# ctecka_brana.net
KiCad netlist of a schematic drawn in EAGLE
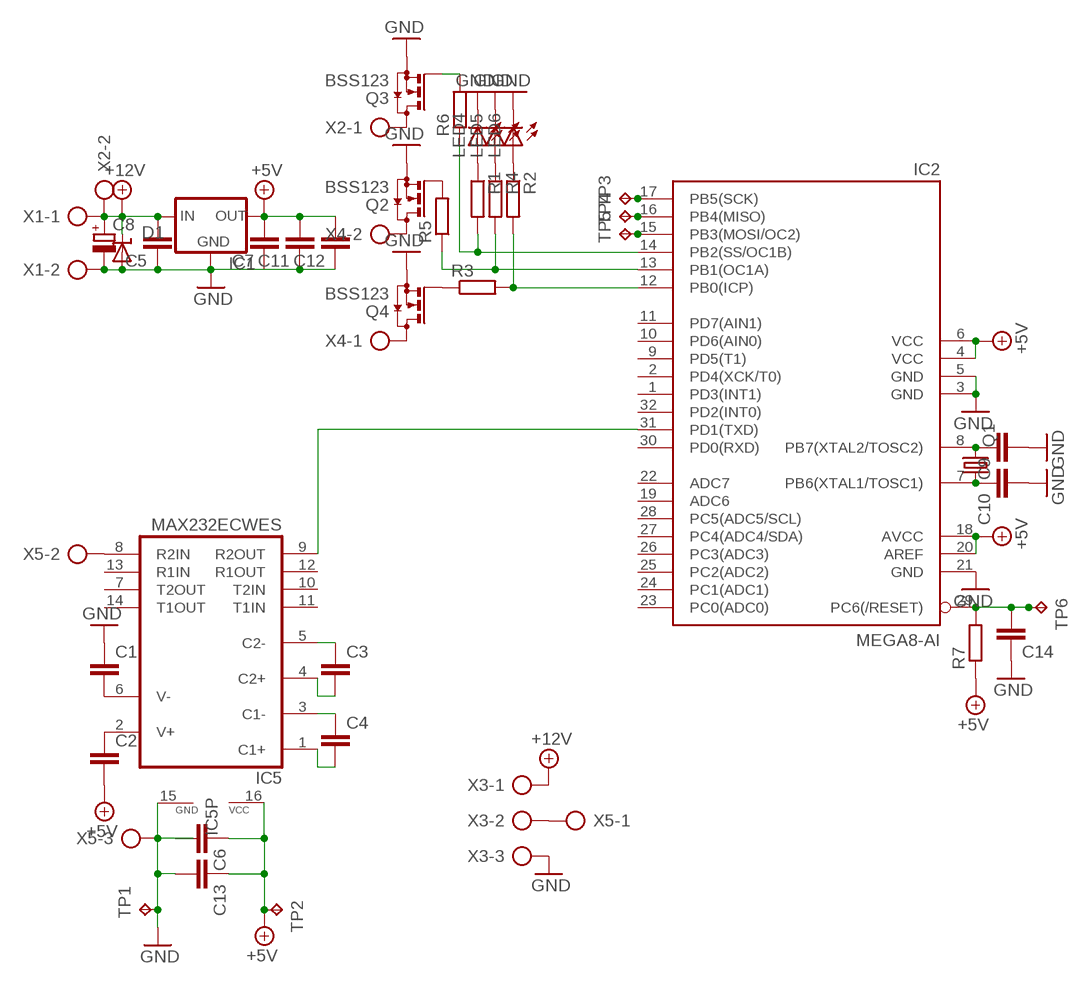
[diagram p0: schematic, sheet 1]

(export (version "E")
  (design (tool "Eeschema 10.0.6"))
  (components
    (comp (ref "C1")
      (value "C-EUC0603")
      (footprint "eagle-import:C0603")
      (libsource (lib "eagle-import") (part "C-EUC0603"))
    )
    (comp (ref "C2")
      (value "C-EUC0603")
      (footprint "eagle-import:C0603")
      (libsource (lib "eagle-import") (part "C-EUC0603"))
    )
    (comp (ref "C3")
      (value "C-EUC0603")
      (footprint "eagle-import:C0603")
      (libsource (lib "eagle-import") (part "C-EUC0603"))
    )
    (comp (ref "C4")
      (value "C-EUC0603")
      (footprint "eagle-import:C0603")
      (libsource (lib "eagle-import") (part "C-EUC0603"))
    )
    (comp (ref "C5")
      (value "C-EUC0603")
      (footprint "eagle-import:C0603")
      (libsource (lib "eagle-import") (part "C-EUC0603"))
    )
    (comp (ref "C6")
      (value "C-EUC0603")
      (footprint "eagle-import:C0603")
      (libsource (lib "eagle-import") (part "C-EUC0603"))
    )
    (comp (ref "C7")
      (value "C-EUC0603")
      (footprint "eagle-import:C0603")
      (libsource (lib "eagle-import") (part "C-EUC0603"))
    )
    (comp (ref "C8")
      (value "CPOL-EUSMCD")
      (footprint "eagle-import:SMC_D")
      (libsource (lib "eagle-import") (part "CPOL-EUSMCD"))
    )
    (comp (ref "C9")
      (value "C-EUC0603")
      (footprint "eagle-import:C0603")
      (libsource (lib "eagle-import") (part "C-EUC0603"))
    )
    (comp (ref "C10")
      (value "C-EUC0603")
      (footprint "eagle-import:C0603")
      (libsource (lib "eagle-import") (part "C-EUC0603"))
    )
    (comp (ref "C11")
      (value "C-EUC0603")
      (footprint "eagle-import:C0603")
      (libsource (lib "eagle-import") (part "C-EUC0603"))
    )
    (comp (ref "C12")
      (value "C-EUC0603")
      (footprint "eagle-import:C0603")
      (libsource (lib "eagle-import") (part "C-EUC0603"))
    )
    (comp (ref "C13")
      (value "C-EUC0603")
      (footprint "eagle-import:C0603")
      (libsource (lib "eagle-import") (part "C-EUC0603"))
    )
    (comp (ref "C14")
      (value "C-EUC0603")
      (footprint "eagle-import:C0603")
      (libsource (lib "eagle-import") (part "C-EUC0603"))
    )
    (comp (ref "D1")
      (value "SUPPRESSOR-SMBG")
      (footprint "eagle-import:SMBG")
      (libsource (lib "eagle-import") (part "SUPPRESSOR-SMBG"))
    )
    (comp (ref "IC1")
      (value "78LXXF")
      (footprint "eagle-import:SOT89R")
      (libsource (lib "eagle-import") (part "78LXXF"))
    )
    (comp (ref "IC2")
      (value "MEGA8-AI")
      (footprint "eagle-import:TQFP32-08")
      (libsource (lib "eagle-import") (part "MEGA8-AI"))
    )
    (comp (ref "IC5")
      (value "MAX232ECWES")
      (footprint "eagle-import:SO16")
      (libsource (lib "eagle-import") (part "MAX232ECWES"))
    )
    (comp (ref "LED4")
      (value "LEDCHIP-LED0805")
      (footprint "eagle-import:CHIP-LED0805")
      (libsource (lib "eagle-import") (part "LEDCHIP-LED0805"))
    )
    (comp (ref "LED5")
      (value "LEDCHIP-LED0805")
      (footprint "eagle-import:CHIP-LED0805")
      (libsource (lib "eagle-import") (part "LEDCHIP-LED0805"))
    )
    (comp (ref "LED6")
      (value "LEDCHIP-LED0805")
      (footprint "eagle-import:CHIP-LED0805")
      (libsource (lib "eagle-import") (part "LEDCHIP-LED0805"))
    )
    (comp (ref "Q1")
      (value "CRYSTALCTS406")
      (footprint "eagle-import:CTS406")
      (libsource (lib "eagle-import") (part "CRYSTALCTS406"))
    )
    (comp (ref "Q2")
      (value "BSS123")
      (footprint "eagle-import:SOT23")
      (libsource (lib "eagle-import") (part "BSS123"))
    )
    (comp (ref "Q3")
      (value "BSS123")
      (footprint "eagle-import:SOT23")
      (libsource (lib "eagle-import") (part "BSS123"))
    )
    (comp (ref "Q4")
      (value "BSS123")
      (footprint "eagle-import:SOT23")
      (libsource (lib "eagle-import") (part "BSS123"))
    )
    (comp (ref "R1")
      (value "R-EU_R0603")
      (footprint "eagle-import:R0603")
      (libsource (lib "eagle-import") (part "R-EU_R0603"))
    )
    (comp (ref "R2")
      (value "R-EU_R0603")
      (footprint "eagle-import:R0603")
      (libsource (lib "eagle-import") (part "R-EU_R0603"))
    )
    (comp (ref "R3")
      (value "R-EU_R0603")
      (footprint "eagle-import:R0603")
      (libsource (lib "eagle-import") (part "R-EU_R0603"))
    )
    (comp (ref "R4")
      (value "R-EU_R0603")
      (footprint "eagle-import:R0603")
      (libsource (lib "eagle-import") (part "R-EU_R0603"))
    )
    (comp (ref "R5")
      (value "R-EU_R0603")
      (footprint "eagle-import:R0603")
      (libsource (lib "eagle-import") (part "R-EU_R0603"))
    )
    (comp (ref "R6")
      (value "R-EU_R0603")
      (footprint "eagle-import:R0603")
      (libsource (lib "eagle-import") (part "R-EU_R0603"))
    )
    (comp (ref "R7")
      (value "R-EU_R0603")
      (footprint "eagle-import:R0603")
      (libsource (lib "eagle-import") (part "R-EU_R0603"))
    )
    (comp (ref "TP1")
      (value "TPB1,27")
      (footprint "eagle-import:B1,27")
      (libsource (lib "eagle-import") (part "TPB1,27"))
    )
    (comp (ref "TP2")
      (value "TPB1,27")
      (footprint "eagle-import:B1,27")
      (libsource (lib "eagle-import") (part "TPB1,27"))
    )
    (comp (ref "TP3")
      (value "TPB1,27")
      (footprint "eagle-import:B1,27")
      (libsource (lib "eagle-import") (part "TPB1,27"))
    )
    (comp (ref "TP4")
      (value "TPB1,27")
      (footprint "eagle-import:B1,27")
      (libsource (lib "eagle-import") (part "TPB1,27"))
    )
    (comp (ref "TP5")
      (value "TPB1,27")
      (footprint "eagle-import:B1,27")
      (libsource (lib "eagle-import") (part "TPB1,27"))
    )
    (comp (ref "TP6")
      (value "TPB1,27")
      (footprint "eagle-import:B1,27")
      (libsource (lib "eagle-import") (part "TPB1,27"))
    )
    (comp (ref "X1")
      (value "AK500/2")
      (footprint "eagle-import:AK500_2")
      (libsource (lib "eagle-import") (part "AK500/2"))
    )
    (comp (ref "X2")
      (value "AK500/2")
      (footprint "eagle-import:AK500_2")
      (libsource (lib "eagle-import") (part "AK500/2"))
    )
    (comp (ref "X3")
      (value "AK500/3")
      (footprint "eagle-import:AK500_3")
      (libsource (lib "eagle-import") (part "AK500/3"))
    )
    (comp (ref "X4")
      (value "AK500/2")
      (footprint "eagle-import:AK500_2")
      (libsource (lib "eagle-import") (part "AK500/2"))
    )
    (comp (ref "X5")
      (value "AK500/3")
      (footprint "eagle-import:AK500_3")
      (libsource (lib "eagle-import") (part "AK500/3"))
    )
  )
  (nets
    (net (code "1") (name "+5V") (class "Default")
      (node (ref "C11") (pin "2") (pinfunction "2_2") (pintype "passive"))
      (node (ref "C12") (pin "2") (pinfunction "2_2") (pintype "passive"))
      (node (ref "C13") (pin "1") (pinfunction "1_1") (pintype "passive"))
      (node (ref "C2") (pin "2") (pinfunction "2_2") (pintype "passive"))
      (node (ref "C6") (pin "1") (pinfunction "1_1") (pintype "passive"))
      (node (ref "C7") (pin "2") (pinfunction "2_2") (pintype "passive"))
      (node (ref "IC1") (pin "2") (pinfunction "OUT_2") (pintype "passive"))
      (node (ref "IC2") (pin "18") (pinfunction "AVCC_18") (pintype "power_in"))
      (node (ref "IC2") (pin "20") (pinfunction "AREF_20") (pintype "passive"))
      (node (ref "IC2") (pin "4") (pinfunction "VCC_4") (pintype "power_in"))
      (node (ref "IC2") (pin "6") (pinfunction "VCC_6") (pintype "power_in"))
      (node (ref "IC5") (pin "16") (pinfunction "VCC_16") (pintype "power_in"))
      (node (ref "R7") (pin "1") (pinfunction "1_1") (pintype "passive"))
      (node (ref "TP2") (pin "TP") (pinfunction "TP_TP") (pintype "input"))
    )
    (net (code "2") (name "+12V") (class "Default")
      (node (ref "C5") (pin "2") (pinfunction "2_2") (pintype "passive"))
      (node (ref "C8") (pin "+") (pinfunction "+_+") (pintype "passive"))
      (node (ref "D1") (pin "C") (pinfunction "C_C") (pintype "passive"))
      (node (ref "IC1") (pin "1") (pinfunction "IN_1") (pintype "input"))
      (node (ref "X1") (pin "1") (pinfunction "KL_1") (pintype "passive"))
      (node (ref "X2") (pin "2") (pinfunction "KL_2") (pintype "passive"))
      (node (ref "X3") (pin "1") (pinfunction "KL_1") (pintype "passive"))
    )
    (net (code "3") (name "GND") (class "Default")
      (node (ref "C1") (pin "1") (pinfunction "1_1") (pintype "passive"))
      (node (ref "C10") (pin "2") (pinfunction "2_2") (pintype "passive"))
      (node (ref "C11") (pin "1") (pinfunction "1_1") (pintype "passive"))
      (node (ref "C12") (pin "1") (pinfunction "1_1") (pintype "passive"))
      (node (ref "C13") (pin "2") (pinfunction "2_2") (pintype "passive"))
      (node (ref "C14") (pin "1") (pinfunction "1_1") (pintype "passive"))
      (node (ref "C5") (pin "1") (pinfunction "1_1") (pintype "passive"))
      (node (ref "C6") (pin "2") (pinfunction "2_2") (pintype "passive"))
      (node (ref "C7") (pin "1") (pinfunction "1_1") (pintype "passive"))
      (node (ref "C8") (pin "-") (pinfunction "-_-") (pintype "passive"))
      (node (ref "C9") (pin "2") (pinfunction "2_2") (pintype "passive"))
      (node (ref "D1") (pin "A") (pinfunction "A_A") (pintype "passive"))
      (node (ref "IC1") (pin "3") (pinfunction "GND_3") (pintype "input"))
      (node (ref "IC2") (pin "21") (pinfunction "GND_21") (pintype "power_in"))
      (node (ref "IC2") (pin "3") (pinfunction "GND_3") (pintype "power_in"))
      (node (ref "IC2") (pin "5") (pinfunction "GND_5") (pintype "power_in"))
      (node (ref "IC5") (pin "15") (pinfunction "GND_15") (pintype "power_in"))
      (node (ref "LED4") (pin "C") (pinfunction "C_C") (pintype "passive"))
      (node (ref "LED5") (pin "C") (pinfunction "C_C") (pintype "passive"))
      (node (ref "LED6") (pin "C") (pinfunction "C_C") (pintype "passive"))
      (node (ref "Q2") (pin "2") (pinfunction "S_2") (pintype "passive"))
      (node (ref "Q3") (pin "2") (pinfunction "S_2") (pintype "passive"))
      (node (ref "Q4") (pin "2") (pinfunction "S_2") (pintype "passive"))
      (node (ref "TP1") (pin "TP") (pinfunction "TP_TP") (pintype "input"))
      (node (ref "X1") (pin "2") (pinfunction "KL_2") (pintype "passive"))
      (node (ref "X3") (pin "3") (pinfunction "KL_3") (pintype "passive"))
      (node (ref "X5") (pin "3") (pinfunction "KL_3") (pintype "passive"))
    )
    (net (code "4") (name "Net-(IC2-PB0(ICP))") (class "Default")
      (node (ref "IC2") (pin "12") (pinfunction "PB0(ICP)_12") (pintype "bidirectional"))
      (node (ref "R2") (pin "2") (pinfunction "2_2") (pintype "passive"))
      (node (ref "R3") (pin "2") (pinfunction "2_2") (pintype "passive"))
    )
    (net (code "5") (name "Net-(IC2-PB1(OC1A))") (class "Default")
      (node (ref "IC2") (pin "13") (pinfunction "PB1(OC1A)_13") (pintype "bidirectional"))
      (node (ref "R4") (pin "2") (pinfunction "2_2") (pintype "passive"))
      (node (ref "R5") (pin "1") (pinfunction "1_1") (pintype "passive"))
    )
    (net (code "6") (name "Net-(IC2-PB2(SS{slash}OC1B))") (class "Default")
      (node (ref "IC2") (pin "14") (pinfunction "PB2(SS/OC1B)_14") (pintype "bidirectional"))
      (node (ref "R1") (pin "2") (pinfunction "2_2") (pintype "passive"))
      (node (ref "R6") (pin "1") (pinfunction "1_1") (pintype "passive"))
    )
    (net (code "7") (name "Net-(IC2-PB3(MOSI{slash}OC2))") (class "Default")
      (node (ref "IC2") (pin "15") (pinfunction "PB3(MOSI/OC2)_15") (pintype "bidirectional"))
      (node (ref "TP5") (pin "TP") (pinfunction "TP_TP") (pintype "input"))
    )
    (net (code "8") (name "Net-(IC2-PB4(MISO))") (class "Default")
      (node (ref "IC2") (pin "16") (pinfunction "PB4(MISO)_16") (pintype "bidirectional"))
      (node (ref "TP4") (pin "TP") (pinfunction "TP_TP") (pintype "input"))
    )
    (net (code "9") (name "Net-(IC2-PB5(SCK))") (class "Default")
      (node (ref "IC2") (pin "17") (pinfunction "PB5(SCK)_17") (pintype "bidirectional"))
      (node (ref "TP3") (pin "TP") (pinfunction "TP_TP") (pintype "input"))
    )
    (net (code "10") (name "Net-(IC2-PB6(XTAL1{slash}TOSC1))") (class "Default")
      (node (ref "C10") (pin "1") (pinfunction "1_1") (pintype "passive"))
      (node (ref "IC2") (pin "7") (pinfunction "PB6(XTAL1/TOSC1)_7") (pintype "bidirectional"))
      (node (ref "Q1") (pin "1") (pinfunction "1_1") (pintype "passive"))
    )
    (net (code "11") (name "Net-(IC2-PB7(XTAL2{slash}TOSC2))") (class "Default")
      (node (ref "C9") (pin "1") (pinfunction "1_1") (pintype "passive"))
      (node (ref "IC2") (pin "8") (pinfunction "PB7(XTAL2/TOSC2)_8") (pintype "bidirectional"))
      (node (ref "Q1") (pin "3") (pinfunction "2_3") (pintype "passive"))
    )
    (net (code "12") (name "Net-(IC2-PC6({slash}RESET))") (class "Default")
      (node (ref "C14") (pin "2") (pinfunction "2_2") (pintype "passive"))
      (node (ref "IC2") (pin "29") (pinfunction "PC6(/RESET)_29") (pintype "bidirectional"))
      (node (ref "R7") (pin "2") (pinfunction "2_2") (pintype "passive"))
      (node (ref "TP6") (pin "TP") (pinfunction "TP_TP") (pintype "input"))
    )
    (net (code "13") (name "Net-(IC2-PD1(TXD))") (class "Default")
      (node (ref "IC2") (pin "31") (pinfunction "PD1(TXD)_31") (pintype "bidirectional"))
      (node (ref "IC5") (pin "9") (pinfunction "R2OUT_9") (pintype "output"))
    )
    (net (code "14") (name "Net-(IC5A-C1+)") (class "Default")
      (node (ref "C4") (pin "2") (pinfunction "2_2") (pintype "passive"))
      (node (ref "IC5") (pin "1") (pinfunction "C1+_1") (pintype "bidirectional"))
    )
    (net (code "15") (name "Net-(IC5A-C1-)") (class "Default")
      (node (ref "C4") (pin "1") (pinfunction "1_1") (pintype "passive"))
      (node (ref "IC5") (pin "3") (pinfunction "C1-_3") (pintype "bidirectional"))
    )
    (net (code "16") (name "Net-(IC5A-C2+)") (class "Default")
      (node (ref "C3") (pin "2") (pinfunction "2_2") (pintype "passive"))
      (node (ref "IC5") (pin "4") (pinfunction "C2+_4") (pintype "bidirectional"))
    )
    (net (code "17") (name "Net-(IC5A-C2-)") (class "Default")
      (node (ref "C3") (pin "1") (pinfunction "1_1") (pintype "passive"))
      (node (ref "IC5") (pin "5") (pinfunction "C2-_5") (pintype "bidirectional"))
    )
    (net (code "18") (name "Net-(IC5A-R2IN)") (class "Default")
      (node (ref "IC5") (pin "8") (pinfunction "R2IN_8") (pintype "input"))
      (node (ref "X5") (pin "2") (pinfunction "KL_2") (pintype "passive"))
    )
    (net (code "19") (name "Net-(IC5A-V+)") (class "Default")
      (node (ref "C2") (pin "1") (pinfunction "1_1") (pintype "passive"))
      (node (ref "IC5") (pin "2") (pinfunction "V+_2") (pintype "bidirectional"))
    )
    (net (code "20") (name "Net-(IC5A-V-)") (class "Default")
      (node (ref "C1") (pin "2") (pinfunction "2_2") (pintype "passive"))
      (node (ref "IC5") (pin "6") (pinfunction "V-_6") (pintype "bidirectional"))
    )
    (net (code "21") (name "Net-(LED4-PadA)") (class "Default")
      (node (ref "LED4") (pin "A") (pinfunction "A_A") (pintype "passive"))
      (node (ref "R1") (pin "1") (pinfunction "1_1") (pintype "passive"))
    )
    (net (code "22") (name "Net-(LED5-PadA)") (class "Default")
      (node (ref "LED5") (pin "A") (pinfunction "A_A") (pintype "passive"))
      (node (ref "R4") (pin "1") (pinfunction "1_1") (pintype "passive"))
    )
    (net (code "23") (name "Net-(LED6-PadA)") (class "Default")
      (node (ref "LED6") (pin "A") (pinfunction "A_A") (pintype "passive"))
      (node (ref "R2") (pin "1") (pinfunction "1_1") (pintype "passive"))
    )
    (net (code "24") (name "Net-(Q2-D)") (class "Default")
      (node (ref "Q2") (pin "3") (pinfunction "D_3") (pintype "passive"))
      (node (ref "X4") (pin "2") (pinfunction "KL_2") (pintype "passive"))
    )
    (net (code "25") (name "Net-(Q2-G)") (class "Default")
      (node (ref "Q2") (pin "1") (pinfunction "G_1") (pintype "passive"))
      (node (ref "R5") (pin "2") (pinfunction "2_2") (pintype "passive"))
    )
    (net (code "26") (name "Net-(Q3-D)") (class "Default")
      (node (ref "Q3") (pin "3") (pinfunction "D_3") (pintype "passive"))
      (node (ref "X2") (pin "1") (pinfunction "KL_1") (pintype "passive"))
    )
    (net (code "27") (name "Net-(Q3-G)") (class "Default")
      (node (ref "Q3") (pin "1") (pinfunction "G_1") (pintype "passive"))
      (node (ref "R6") (pin "2") (pinfunction "2_2") (pintype "passive"))
    )
    (net (code "28") (name "Net-(Q4-D)") (class "Default")
      (node (ref "Q4") (pin "3") (pinfunction "D_3") (pintype "passive"))
      (node (ref "X4") (pin "1") (pinfunction "KL_1") (pintype "passive"))
    )
    (net (code "29") (name "Net-(Q4-G)") (class "Default")
      (node (ref "Q4") (pin "1") (pinfunction "G_1") (pintype "passive"))
      (node (ref "R3") (pin "1") (pinfunction "1_1") (pintype "passive"))
    )
    (net (code "30") (name "Net-(X3B-KL)") (class "Default")
      (node (ref "X3") (pin "2") (pinfunction "KL_2") (pintype "passive"))
      (node (ref "X5") (pin "1") (pinfunction "KL_1") (pintype "passive"))
    )
    (net (code "31") (name "unconnected-(IC2-ADC6-Pad19)") (class "Default")
      (node (ref "IC2") (pin "19") (pinfunction "ADC6_19") (pintype "bidirectional"))
    )
    (net (code "32") (name "unconnected-(IC2-ADC7-Pad22)") (class "Default")
      (node (ref "IC2") (pin "22") (pinfunction "ADC7_22") (pintype "bidirectional"))
    )
    (net (code "33") (name "unconnected-(IC2-PC0(ADC0)-Pad23)") (class "Default")
      (node (ref "IC2") (pin "23") (pinfunction "PC0(ADC0)_23") (pintype "bidirectional"))
    )
    (net (code "34") (name "unconnected-(IC2-PC1(ADC1)-Pad24)") (class "Default")
      (node (ref "IC2") (pin "24") (pinfunction "PC1(ADC1)_24") (pintype "bidirectional"))
    )
    (net (code "35") (name "unconnected-(IC2-PC2(ADC2)-Pad25)") (class "Default")
      (node (ref "IC2") (pin "25") (pinfunction "PC2(ADC2)_25") (pintype "bidirectional"))
    )
    (net (code "36") (name "unconnected-(IC2-PC3(ADC3)-Pad26)") (class "Default")
      (node (ref "IC2") (pin "26") (pinfunction "PC3(ADC3)_26") (pintype "bidirectional"))
    )
    (net (code "37") (name "unconnected-(IC2-PC4(ADC4{slash}SDA)-Pad27)") (class "Default")
      (node (ref "IC2") (pin "27") (pinfunction "PC4(ADC4/SDA)_27") (pintype "bidirectional"))
    )
    (net (code "38") (name "unconnected-(IC2-PC5(ADC5{slash}SCL)-Pad28)") (class "Default")
      (node (ref "IC2") (pin "28") (pinfunction "PC5(ADC5/SCL)_28") (pintype "bidirectional"))
    )
    (net (code "39") (name "unconnected-(IC2-PD0(RXD)-Pad30)") (class "Default")
      (node (ref "IC2") (pin "30") (pinfunction "PD0(RXD)_30") (pintype "bidirectional"))
    )
    (net (code "40") (name "unconnected-(IC2-PD2(INT0)-Pad32)") (class "Default")
      (node (ref "IC2") (pin "32") (pinfunction "PD2(INT0)_32") (pintype "bidirectional"))
    )
    (net (code "41") (name "unconnected-(IC2-PD3(INT1)-Pad1)") (class "Default")
      (node (ref "IC2") (pin "1") (pinfunction "PD3(INT1)_1") (pintype "bidirectional"))
    )
    (net (code "42") (name "unconnected-(IC2-PD4(XCK{slash}T0)-Pad2)") (class "Default")
      (node (ref "IC2") (pin "2") (pinfunction "PD4(XCK/T0)_2") (pintype "bidirectional"))
    )
    (net (code "43") (name "unconnected-(IC2-PD5(T1)-Pad9)") (class "Default")
      (node (ref "IC2") (pin "9") (pinfunction "PD5(T1)_9") (pintype "bidirectional"))
    )
    (net (code "44") (name "unconnected-(IC2-PD6(AIN0)-Pad10)") (class "Default")
      (node (ref "IC2") (pin "10") (pinfunction "PD6(AIN0)_10") (pintype "bidirectional"))
    )
    (net (code "45") (name "unconnected-(IC2-PD7(AIN1)-Pad11)") (class "Default")
      (node (ref "IC2") (pin "11") (pinfunction "PD7(AIN1)_11") (pintype "bidirectional"))
    )
    (net (code "46") (name "unconnected-(IC5A-R1IN-Pad13)") (class "Default")
      (node (ref "IC5") (pin "13") (pinfunction "R1IN_13") (pintype "input"))
    )
    (net (code "47") (name "unconnected-(IC5A-R1OUT-Pad12)") (class "Default")
      (node (ref "IC5") (pin "12") (pinfunction "R1OUT_12") (pintype "output"))
    )
    (net (code "48") (name "unconnected-(IC5A-T1IN-Pad11)") (class "Default")
      (node (ref "IC5") (pin "11") (pinfunction "T1IN_11") (pintype "input"))
    )
    (net (code "49") (name "unconnected-(IC5A-T1OUT-Pad14)") (class "Default")
      (node (ref "IC5") (pin "14") (pinfunction "T1OUT_14") (pintype "output"))
    )
    (net (code "50") (name "unconnected-(IC5A-T2IN-Pad10)") (class "Default")
      (node (ref "IC5") (pin "10") (pinfunction "T2IN_10") (pintype "input"))
    )
    (net (code "51") (name "unconnected-(IC5A-T2OUT-Pad7)") (class "Default")
      (node (ref "IC5") (pin "7") (pinfunction "T2OUT_7") (pintype "output"))
    )
  )
)
